# Bluetooth_mersasV2.net
KiCad netlist of a schematic drawn in Altium Designer
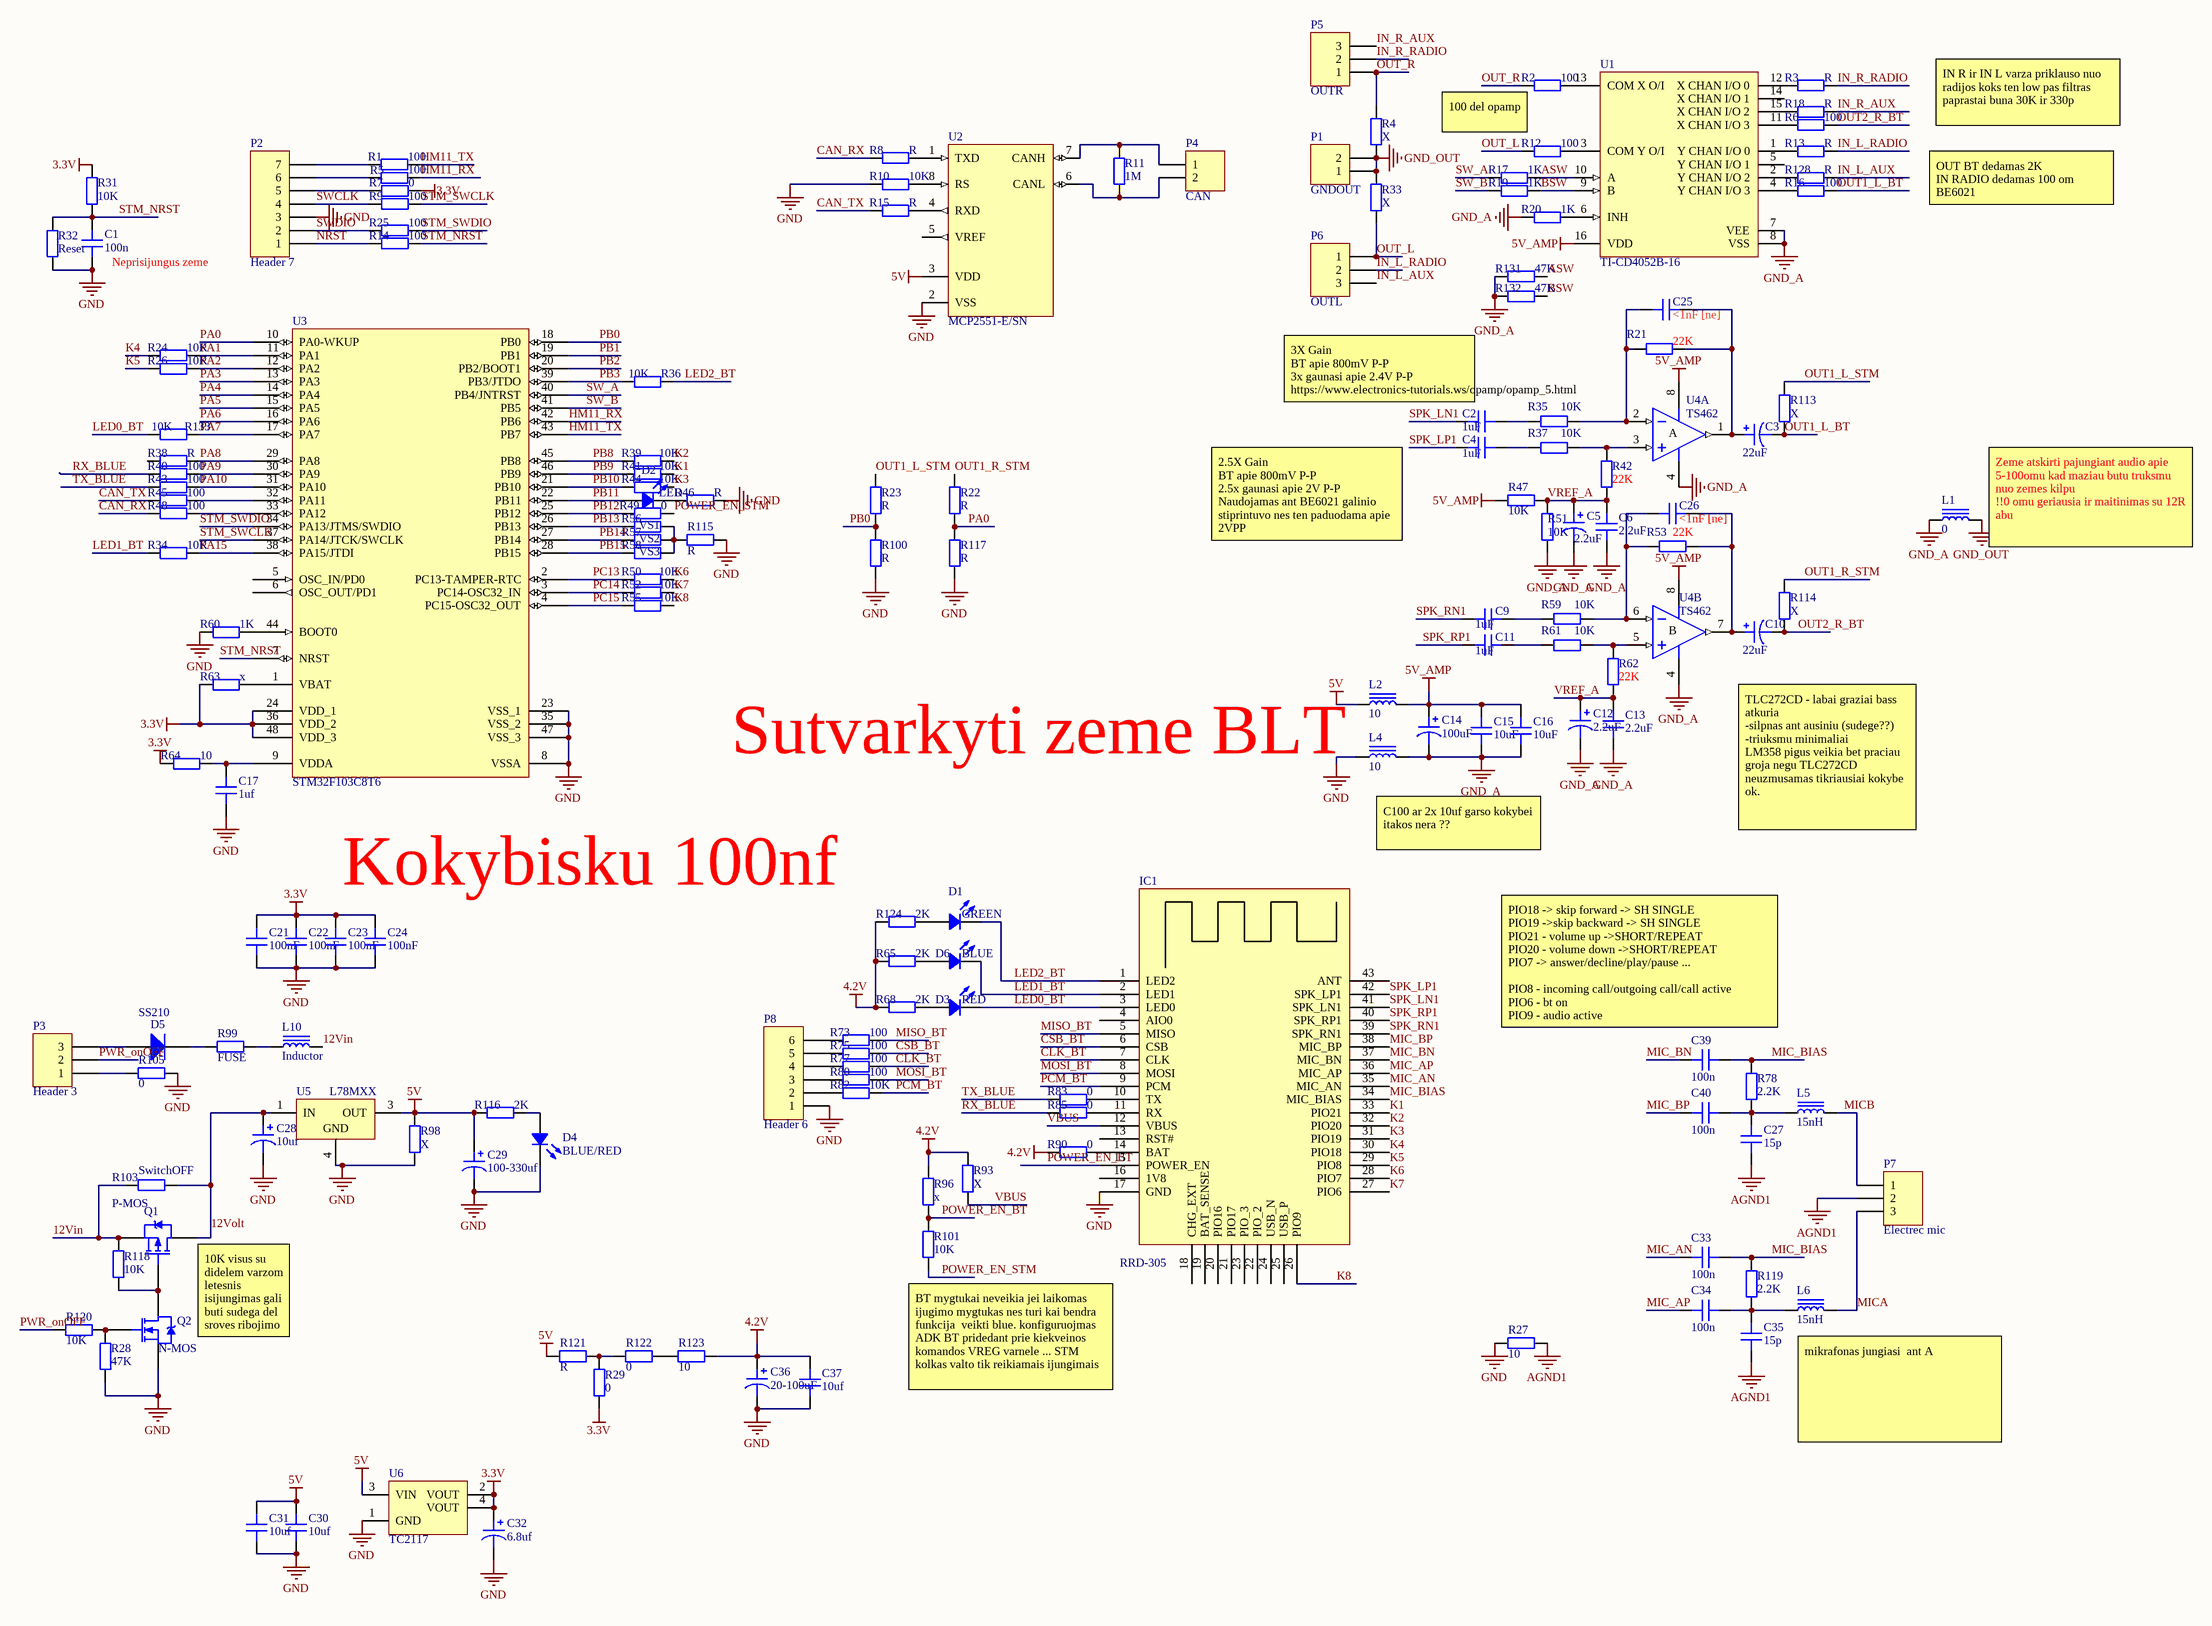
[diagram p0: Bluetooth_mersasV2.SchDoc]

(export (version "E")
  (design (tool "Eeschema 10.0.6"))
  (components
    (comp (ref "C1")
      (value "100n")
      (footprint "CAP 0603/1608")
      (description "Ceramic capacitor")
      (libsource (lib "Pasyviniai_RCL") (part "C"))
    )
    (comp (ref "C2")
      (value "1uF")
      (footprint "CAP 0805/2012")
      (description "Ceramic capacitor")
      (libsource (lib "Pasyviniai_RCL") (part "C"))
    )
    (comp (ref "C3")
      (value "22uF")
      (footprint "TANT A size")
      (description "Polarised Capacitor")
      (libsource (lib "") (part "Cpola_1"))
    )
    (comp (ref "C4")
      (value "1uF")
      (footprint "CAP 0805/2012")
      (description "Ceramic capacitor")
      (libsource (lib "Pasyviniai_RCL") (part "C"))
    )
    (comp (ref "C5")
      (value "2.2uF")
      (footprint "TANT R(2824)")
      (description "Polarised Capacitor")
      (libsource (lib "Pasyviniai_RCL") (part "Cpola"))
    )
    (comp (ref "C6")
      (value "2.2uF")
      (footprint "CAP 0805/2012")
      (description "Ceramic capacitor")
      (libsource (lib "Pasyviniai_RCL") (part "C"))
    )
    (comp (ref "C9")
      (value "1uF")
      (footprint "CAP 0805/2012")
      (description "Ceramic capacitor")
      (libsource (lib "Pasyviniai_RCL") (part "C"))
    )
    (comp (ref "C10")
      (value "22uF")
      (footprint "TANT A size")
      (description "Polarised Capacitor")
      (libsource (lib "") (part "Cpola_1"))
    )
    (comp (ref "C11")
      (value "1uF")
      (footprint "CAP 0805/2012")
      (description "Ceramic capacitor")
      (libsource (lib "Pasyviniai_RCL") (part "C"))
    )
    (comp (ref "C12")
      (value "2.2uF")
      (footprint "TANT R(2824)")
      (description "Polarised Capacitor")
      (libsource (lib "Pasyviniai_RCL") (part "Cpola"))
    )
    (comp (ref "C13")
      (value "2.2uF")
      (footprint "CAP 0805/2012")
      (description "Ceramic capacitor")
      (libsource (lib "Pasyviniai_RCL") (part "C"))
    )
    (comp (ref "C14")
      (value "100uF")
      (footprint "tant B size")
      (description "Polarised Capacitor")
      (libsource (lib "Pasyviniai_RCL") (part "Cpola"))
    )
    (comp (ref "C15")
      (value "10uF")
      (footprint "CAP 1206/3216")
      (description "Ceramic capacitor")
      (libsource (lib "Pasyviniai_RCL") (part "C"))
    )
    (comp (ref "C16")
      (value "10uF")
      (footprint "CAP 1206/3216")
      (description "Ceramic capacitor")
      (libsource (lib "Pasyviniai_RCL") (part "C"))
    )
    (comp (ref "C17")
      (value "1uf")
      (footprint "CAP 0805/2012")
      (description "Ceramic capacitor")
      (libsource (lib "Pasyviniai_RCL") (part "C"))
    )
    (comp (ref "C21")
      (value "100nF")
      (footprint "CAP 0603/1608")
      (description "Ceramic capacitor")
      (libsource (lib "Pasyviniai_RCL") (part "C"))
    )
    (comp (ref "C22")
      (value "100nF")
      (footprint "CAP 0603/1608")
      (description "Ceramic capacitor")
      (libsource (lib "Pasyviniai_RCL") (part "C"))
    )
    (comp (ref "C23")
      (value "100nF")
      (footprint "CAP 0603/1608")
      (description "Ceramic capacitor")
      (libsource (lib "Pasyviniai_RCL") (part "C"))
    )
    (comp (ref "C24")
      (value "100nF")
      (footprint "CAP 0603/1608")
      (description "Ceramic capacitor")
      (libsource (lib "Pasyviniai_RCL") (part "C"))
    )
    (comp (ref "C25")
      (value "<1nF [ne]")
      (footprint "CAP 0805/2012")
      (description "Ceramic capacitor")
      (libsource (lib "Pasyviniai_RCL") (part "C"))
    )
    (comp (ref "C26")
      (value "<1nF [ne]")
      (footprint "CAP 0805/2012")
      (description "Ceramic capacitor")
      (libsource (lib "Pasyviniai_RCL") (part "C"))
    )
    (comp (ref "C27")
      (value "15p")
      (footprint "CAP 0603/1608")
      (description "Ceramic capacitor")
      (libsource (lib "Pasyviniai_RCL") (part "C"))
    )
    (comp (ref "C28")
      (value "10uf")
      (footprint "CAP POL 2917/7343")
      (description "Polarised Capacitor")
      (libsource (lib "Pasyviniai_RCL") (part "Cpola"))
    )
    (comp (ref "C29")
      (value "100-330uf")
      (footprint "CAP POL 2917/7343")
      (description "Polarised Capacitor")
      (libsource (lib "Pasyviniai_RCL") (part "Cpola"))
    )
    (comp (ref "C30")
      (value "10uf")
      (footprint "CAP 1210/3225")
      (description "Ceramic capacitor")
      (libsource (lib "Pasyviniai_RCL") (part "C"))
    )
    (comp (ref "C31")
      (value "10uf")
      (footprint "CAP 1210/3225")
      (description "Ceramic capacitor")
      (libsource (lib "Pasyviniai_RCL") (part "C"))
    )
    (comp (ref "C32")
      (value "6.8uf")
      (footprint "CAP POL 2917/7343")
      (description "Polarised Capacitor")
      (libsource (lib "Pasyviniai_RCL") (part "Cpola"))
    )
    (comp (ref "C33")
      (value "100n")
      (footprint "CAP 0603/1608")
      (description "Ceramic capacitor")
      (libsource (lib "Pasyviniai_RCL") (part "C"))
    )
    (comp (ref "C34")
      (value "100n")
      (footprint "CAP 0603/1608")
      (description "Ceramic capacitor")
      (libsource (lib "Pasyviniai_RCL") (part "C"))
    )
    (comp (ref "C35")
      (value "15p")
      (footprint "CAP 0603/1608")
      (description "Ceramic capacitor")
      (libsource (lib "Pasyviniai_RCL") (part "C"))
    )
    (comp (ref "C36")
      (value "20-100uF")
      (footprint "tant B size")
      (description "Polarised Capacitor")
      (libsource (lib "Pasyviniai_RCL") (part "Cpola"))
    )
    (comp (ref "C37")
      (value "10uf")
      (footprint "CAP 1206/3216")
      (description "Ceramic capacitor")
      (libsource (lib "Pasyviniai_RCL") (part "C"))
    )
    (comp (ref "C39")
      (value "100n")
      (footprint "CAP 0603/1608")
      (description "Ceramic capacitor")
      (libsource (lib "Pasyviniai_RCL") (part "C"))
    )
    (comp (ref "C40")
      (value "100n")
      (footprint "CAP 0603/1608")
      (description "Ceramic capacitor")
      (libsource (lib "Pasyviniai_RCL") (part "C"))
    )
    (comp (ref "D1")
      (value "GREEN")
      (footprint "LED 0805/2012")
      (description "Chip LED")
      (libsource (lib "Pasyviniai_RCL") (part "LED"))
    )
    (comp (ref "D2")
      (value "LED")
      (footprint "LED 0603/1608")
      (description "Chip LED")
      (libsource (lib "Pasyviniai_RCL") (part "LED"))
    )
    (comp (ref "D3")
      (value "RED")
      (footprint "LED 0805/2012")
      (description "Chip LED")
      (libsource (lib "Pasyviniai_RCL") (part "LED"))
    )
    (comp (ref "D4")
      (value "BLUE/RED")
      (footprint "LED 0805/2012")
      (description "Chip LED")
      (libsource (lib "Pasyviniai_RCL") (part "LED"))
    )
    (comp (ref "D5")
      (value "SS210")
      (footprint "DO214AC SMA")
      (description "Diode")
      (libsource (lib "Pasyviniai_RCL") (part "Diode"))
    )
    (comp (ref "D6")
      (value "BLUE")
      (footprint "LED 0805/2012")
      (description "Chip LED")
      (libsource (lib "Pasyviniai_RCL") (part "LED"))
    )
    (comp (ref "IC1")
      (value "RRD-305")
      (footprint "RRD-305")
      (description "Audio Module Bluetooth 5.0 QCC3005 chip")
      (libsource (lib "Ivairus") (part "RRD-305"))
    )
    (comp (ref "L1")
      (value "0")
      (footprint "IND 1206/3216 - 1.0MM")
      (description "SMT Inductor")
      (libsource (lib "Pasyviniai_RCL") (part "Inductor"))
    )
    (comp (ref "L2")
      (value "10")
      (footprint "IND 1206/3216 - 1.0MM")
      (description "SMT Inductor")
      (libsource (lib "Pasyviniai_RCL") (part "Inductor"))
    )
    (comp (ref "L4")
      (value "10")
      (footprint "IND 1206/3216 - 1.0MM")
      (description "SMT Inductor")
      (libsource (lib "Pasyviniai_RCL") (part "Inductor"))
    )
    (comp (ref "L5")
      (value "15nH")
      (footprint "IND 1206/3216 - 1.0MM")
      (description "SMT Inductor")
      (libsource (lib "Pasyviniai_RCL") (part "Inductor"))
    )
    (comp (ref "L6")
      (value "15nH")
      (footprint "IND 1206/3216 - 1.0MM")
      (description "SMT Inductor")
      (libsource (lib "Pasyviniai_RCL") (part "Inductor"))
    )
    (comp (ref "L10")
      (value "Inductor")
      (footprint "IND 1206/3216 - 1.0MM")
      (description "SMT Inductor")
      (libsource (lib "Pasyviniai_RCL") (part "Inductor"))
    )
    (comp (ref "P1")
      (value "GNDOUT")
      (footprint "HDR1X2")
      (description "Header, 2-Pin")
      (fields (field (name "PUBLISHER") "Altium Limited"))
      (libsource (lib "") (part "Header 2_1"))
    )
    (comp (ref "P2")
      (value "Header 7")
      (footprint "2mm1X7")
      (description "Header, 7-Pin")
      (fields (field (name "PUBLISHER") "Altium Limited"))
      (libsource (lib "PIN_HEADER") (part "Header 7"))
    )
    (comp (ref "P3")
      (value "Header 3")
      (footprint "HDR1X3")
      (description "Header, 3-Pin")
      (fields (field (name "PUBLISHER") "Altium Limited"))
      (libsource (lib "PIN_HEADER") (part "Header 3"))
    )
    (comp (ref "P4")
      (value "CAN")
      (footprint "HDR1X2")
      (description "Header, 2-Pin")
      (fields (field (name "PUBLISHER") "Altium Limited"))
      (libsource (lib "PIN_HEADER") (part "Header 2"))
    )
    (comp (ref "P5")
      (value "OUTR")
      (footprint "HDR1X3")
      (description "Header, 3-Pin")
      (fields (field (name "PUBLISHER") "Altium Limited"))
      (libsource (lib "PIN_HEADER") (part "Header 3"))
    )
    (comp (ref "P6")
      (value "OUTL")
      (footprint "HDR1X3")
      (description "Header, 3-Pin")
      (fields (field (name "PUBLISHER") "Altium Limited"))
      (libsource (lib "") (part "Header 3_2"))
    )
    (comp (ref "P7")
      (value "Electrec mic")
      (footprint "HDR1X3")
      (description "Header, 3-Pin")
      (fields (field (name "PUBLISHER") "Altium Limited"))
      (libsource (lib "") (part "Header 3_1"))
    )
    (comp (ref "P8")
      (value "Header 6")
      (footprint "2mm1X6")
      (description "Header, 6-Pin")
      (fields (field (name "PUBLISHER") "Altium Limited"))
      (libsource (lib "PIN_HEADER") (part "Header 6"))
    )
    (comp (ref "Q1")
      (value "P-MOS")
      (footprint "TI SOT-23-3 DBZ")
      (description "Power MOSFET 1GAte 2Source 3 DRAIN")
      (fields (field (name "PUBLISHER") "Altium Limited"))
      (libsource (lib "Aktyviniai") (part "Mosfet-Pch SOT23"))
    )
    (comp (ref "Q2")
      (value "N-MOS")
      (footprint "TI SOT-23-3 DBZ")
      (description "Power MOSFET 1GAte 2Source 3 DRAIN")
      (fields (field (name "PUBLISHER") "Altium Limited"))
      (libsource (lib "Aktyviniai") (part "Mosfet-Nch SOT23"))
    )
    (comp (ref "R1")
      (value "100")
      (footprint "RES 0603/1608")
      (description "Resistor")
      (libsource (lib "") (part "R_1"))
    )
    (comp (ref "R2")
      (value "100")
      (footprint "RES 0805/2012")
      (description "Resistor")
      (libsource (lib "") (part "R_1"))
    )
    (comp (ref "R3")
      (value "R")
      (footprint "RES 0805/2012")
      (description "Resistor")
      (libsource (lib "") (part "R_1"))
    )
    (comp (ref "R4")
      (value "X")
      (footprint "RES 0805/2012")
      (description "Resistor")
      (libsource (lib "Pasyviniai_RCL") (part "R"))
    )
    (comp (ref "R5")
      (value "100")
      (footprint "RES 0603/1608")
      (description "Resistor")
      (libsource (lib "") (part "R_1"))
    )
    (comp (ref "R6")
      (value "100")
      (footprint "RES 0805/2012")
      (description "Resistor")
      (libsource (lib "") (part "R_1"))
    )
    (comp (ref "R7")
      (value "0")
      (footprint "RES 0603/1608")
      (description "Resistor")
      (libsource (lib "") (part "R_1"))
    )
    (comp (ref "R8")
      (value "R")
      (footprint "RES 0805/2012")
      (description "Resistor")
      (libsource (lib "") (part "R_1"))
    )
    (comp (ref "R9")
      (value "100")
      (footprint "RES 0603/1608")
      (description "Resistor")
      (libsource (lib "") (part "R_1"))
    )
    (comp (ref "R10")
      (value "10K")
      (footprint "RES 0805/2012")
      (description "Resistor")
      (libsource (lib "") (part "R_1"))
    )
    (comp (ref "R11")
      (value "1M")
      (footprint "RES 0603/1608")
      (description "Resistor")
      (libsource (lib "Pasyviniai_RCL") (part "R"))
    )
    (comp (ref "R12")
      (value "100")
      (footprint "RES 0805/2012")
      (description "Resistor")
      (libsource (lib "") (part "R_1"))
    )
    (comp (ref "R13")
      (value "R")
      (footprint "RES 0805/2012")
      (description "Resistor")
      (libsource (lib "") (part "R_1"))
    )
    (comp (ref "R14")
      (value "100")
      (footprint "RES 0603/1608")
      (description "Resistor")
      (libsource (lib "") (part "R_1"))
    )
    (comp (ref "R15")
      (value "R")
      (footprint "RES 0603/1608")
      (description "Resistor")
      (libsource (lib "") (part "R_1"))
    )
    (comp (ref "R16")
      (value "100")
      (footprint "RES 0805/2012")
      (description "Resistor")
      (libsource (lib "") (part "R_1"))
    )
    (comp (ref "R17")
      (value "1K")
      (footprint "RES 0603/1608")
      (description "Resistor")
      (libsource (lib "") (part "R_1"))
    )
    (comp (ref "R18")
      (value "R")
      (footprint "RES 0805/2012")
      (description "Resistor")
      (libsource (lib "") (part "R_1"))
    )
    (comp (ref "R19")
      (value "1K")
      (footprint "RES 0603/1608")
      (description "Resistor")
      (libsource (lib "") (part "R_1"))
    )
    (comp (ref "R20")
      (value "1K")
      (footprint "RES 0603/1608")
      (description "Resistor")
      (libsource (lib "") (part "R_1"))
    )
    (comp (ref "R21")
      (value "22K")
      (footprint "RES 0805/2012")
      (description "Resistor")
      (libsource (lib "") (part "R_1"))
    )
    (comp (ref "R22")
      (value "R")
      (footprint "RES 0603/1608")
      (description "Resistor")
      (libsource (lib "Pasyviniai_RCL") (part "R"))
    )
    (comp (ref "R23")
      (value "R")
      (footprint "RES 0603/1608")
      (description "Resistor")
      (libsource (lib "Pasyviniai_RCL") (part "R"))
    )
    (comp (ref "R24")
      (value "10K")
      (footprint "RES 0603/1608")
      (description "Resistor")
      (libsource (lib "") (part "R_1"))
    )
    (comp (ref "R25")
      (value "100")
      (footprint "RES 0805/2012")
      (description "Resistor")
      (libsource (lib "") (part "R_1"))
    )
    (comp (ref "R26")
      (value "10K")
      (footprint "RES 0603/1608")
      (description "Resistor")
      (libsource (lib "") (part "R_1"))
    )
    (comp (ref "R27")
      (value "10")
      (footprint "RES 0805/2012")
      (description "Resistor")
      (libsource (lib "") (part "R_3"))
    )
    (comp (ref "R28")
      (value "47K")
      (footprint "RES 0603/1608")
      (description "Resistor")
      (libsource (lib "") (part "R_2"))
    )
    (comp (ref "R29")
      (value "0")
      (footprint "RES 1206/3216")
      (description "Resistor")
      (libsource (lib "Pasyviniai_RCL") (part "R"))
    )
    (comp (ref "R31")
      (value "10K")
      (footprint "RES 0603/1608")
      (description "Resistor")
      (libsource (lib "") (part "R_2"))
    )
    (comp (ref "R32")
      (value "Reset")
      (footprint "RES 0805/2012")
      (description "Resistor")
      (libsource (lib "") (part "R_2"))
    )
    (comp (ref "R33")
      (value "X")
      (footprint "RES 0805/2012")
      (description "Resistor")
      (libsource (lib "Pasyviniai_RCL") (part "R"))
    )
    (comp (ref "R34")
      (value "10K")
      (footprint "RES 0603/1608")
      (description "Resistor")
      (libsource (lib "") (part "R_1"))
    )
    (comp (ref "R35")
      (value "10K")
      (footprint "RES 0805/2012")
      (description "Resistor")
      (libsource (lib "") (part "R_1"))
    )
    (comp (ref "R36")
      (value "10K")
      (footprint "RES 0603/1608")
      (description "Resistor")
      (libsource (lib "") (part "R_3"))
    )
    (comp (ref "R37")
      (value "10K")
      (footprint "RES 0805/2012")
      (description "Resistor")
      (libsource (lib "") (part "R_1"))
    )
    (comp (ref "R38")
      (value "R")
      (footprint "RES 0603/1608")
      (description "Resistor")
      (libsource (lib "") (part "R_1"))
    )
    (comp (ref "R39")
      (value "10K")
      (footprint "RES 0603/1608")
      (description "Resistor")
      (libsource (lib "") (part "R_1"))
    )
    (comp (ref "R40")
      (value "100")
      (footprint "RES 0603/1608")
      (description "Resistor")
      (libsource (lib "") (part "R_1"))
    )
    (comp (ref "R41")
      (value "10K")
      (footprint "RES 0603/1608")
      (description "Resistor")
      (libsource (lib "") (part "R_1"))
    )
    (comp (ref "R42")
      (value "22K")
      (footprint "RES 0805/2012")
      (description "Resistor")
      (libsource (lib "Pasyviniai_RCL") (part "R"))
    )
    (comp (ref "R43")
      (value "100")
      (footprint "RES 0603/1608")
      (description "Resistor")
      (libsource (lib "") (part "R_1"))
    )
    (comp (ref "R44")
      (value "10K")
      (footprint "RES 0603/1608")
      (description "Resistor")
      (libsource (lib "") (part "R_1"))
    )
    (comp (ref "R45")
      (value "100")
      (footprint "RES 0603/1608")
      (description "Resistor")
      (libsource (lib "") (part "R_1"))
    )
    (comp (ref "R46")
      (value "R")
      (footprint "RES 0603/1608")
      (description "Resistor")
      (libsource (lib "") (part "R_1"))
    )
    (comp (ref "R47")
      (value "10K")
      (footprint "RES 0805/2012")
      (description "Resistor")
      (libsource (lib "") (part "R_3"))
    )
    (comp (ref "R48")
      (value "100")
      (footprint "RES 0603/1608")
      (description "Resistor")
      (libsource (lib "") (part "R_1"))
    )
    (comp (ref "R49")
      (value "0")
      (footprint "RES 0603/1608")
      (description "Resistor")
      (libsource (lib "") (part "R_1"))
    )
    (comp (ref "R50")
      (value "10K")
      (footprint "RES 0603/1608")
      (description "Resistor")
      (libsource (lib "") (part "R_1"))
    )
    (comp (ref "R51")
      (value "10K")
      (footprint "RES 0805/2012")
      (description "Resistor")
      (libsource (lib "") (part "R_2"))
    )
    (comp (ref "R52")
      (value "10K")
      (footprint "RES 0603/1608")
      (description "Resistor")
      (libsource (lib "") (part "R_1"))
    )
    (comp (ref "R53")
      (value "22K")
      (footprint "RES 0805/2012")
      (description "Resistor")
      (libsource (lib "") (part "R_1"))
    )
    (comp (ref "R55")
      (value "10K")
      (footprint "RES 0603/1608")
      (description "Resistor")
      (libsource (lib "") (part "R_1"))
    )
    (comp (ref "R56")
      (value "VS1")
      (footprint "RES 0603/1608")
      (description "Resistor")
      (libsource (lib "") (part "R_1"))
    )
    (comp (ref "R57")
      (value "VS2")
      (footprint "RES 0603/1608")
      (description "Resistor")
      (libsource (lib "") (part "R_1"))
    )
    (comp (ref "R58")
      (value "VS3")
      (footprint "RES 0603/1608")
      (description "Resistor")
      (libsource (lib "") (part "R_1"))
    )
    (comp (ref "R59")
      (value "10K")
      (footprint "RES 0805/2012")
      (description "Resistor")
      (libsource (lib "") (part "R_1"))
    )
    (comp (ref "R60")
      (value "1K")
      (footprint "RES 0603/1608")
      (description "Resistor")
      (libsource (lib "") (part "R_1"))
    )
    (comp (ref "R61")
      (value "10K")
      (footprint "RES 0805/2012")
      (description "Resistor")
      (libsource (lib "") (part "R_1"))
    )
    (comp (ref "R62")
      (value "22K")
      (footprint "RES 0805/2012")
      (description "Resistor")
      (libsource (lib "Pasyviniai_RCL") (part "R"))
    )
    (comp (ref "R63")
      (value "x")
      (footprint "RES 0603/1608")
      (description "Resistor")
      (libsource (lib "") (part "R_1"))
    )
    (comp (ref "R64")
      (value "10")
      (footprint "RES 1206/3216")
      (description "Resistor")
      (libsource (lib "") (part "R_1"))
    )
    (comp (ref "R65")
      (value "2K")
      (footprint "RES 0805/2012")
      (description "Resistor")
      (libsource (lib "") (part "R_1"))
    )
    (comp (ref "R68")
      (value "2K")
      (footprint "RES 0805/2012")
      (description "Resistor")
      (libsource (lib "") (part "R_1"))
    )
    (comp (ref "R73")
      (value "100")
      (footprint "RES 0603/1608")
      (description "Resistor")
      (libsource (lib "") (part "R_1"))
    )
    (comp (ref "R75")
      (value "100")
      (footprint "RES 0603/1608")
      (description "Resistor")
      (libsource (lib "") (part "R_1"))
    )
    (comp (ref "R77")
      (value "100")
      (footprint "RES 0603/1608")
      (description "Resistor")
      (libsource (lib "") (part "R_1"))
    )
    (comp (ref "R78")
      (value "2.2K")
      (footprint "RES 0805/2012")
      (description "Resistor")
      (libsource (lib "Pasyviniai_RCL") (part "R"))
    )
    (comp (ref "R80")
      (value "100")
      (footprint "RES 0603/1608")
      (description "Resistor")
      (libsource (lib "") (part "R_1"))
    )
    (comp (ref "R82")
      (value "10K")
      (footprint "RES 0603/1608")
      (description "Resistor")
      (libsource (lib "") (part "R_1"))
    )
    (comp (ref "R83")
      (value "0")
      (footprint "RES 0603/1608")
      (description "Resistor")
      (libsource (lib "") (part "R_1"))
    )
    (comp (ref "R85")
      (value "0")
      (footprint "RES 0603/1608")
      (description "Resistor")
      (libsource (lib "") (part "R_1"))
    )
    (comp (ref "R90")
      (value "0")
      (footprint "RES 0603/1608")
      (description "Resistor")
      (libsource (lib "") (part "R_1"))
    )
    (comp (ref "R93")
      (value "X")
      (footprint "RES 0603/1608")
      (description "Resistor")
      (libsource (lib "") (part "R_2"))
    )
    (comp (ref "R96")
      (value "x")
      (footprint "RES 0603/1608")
      (description "Resistor")
      (libsource (lib "Pasyviniai_RCL") (part "R"))
    )
    (comp (ref "R98")
      (value "X")
      (footprint "RES 1206/3216")
      (description "Resistor")
      (libsource (lib "Pasyviniai_RCL") (part "R"))
    )
    (comp (ref "R99")
      (value "FUSE")
      (footprint "RES 1206/3216")
      (description "Resistor")
      (libsource (lib "") (part "R_3"))
    )
    (comp (ref "R100")
      (value "R")
      (footprint "RES 0603/1608")
      (description "Resistor")
      (libsource (lib "Pasyviniai_RCL") (part "R"))
    )
    (comp (ref "R101")
      (value "10K")
      (footprint "RES 0603/1608")
      (description "Resistor")
      (libsource (lib "Pasyviniai_RCL") (part "R"))
    )
    (comp (ref "R103")
      (value "SwitchOFF")
      (footprint "RES 0805/2012")
      (description "Resistor")
      (libsource (lib "") (part "R_3"))
    )
    (comp (ref "R105")
      (value "0")
      (footprint "RES 1206/3216")
      (description "Resistor")
      (libsource (lib "") (part "R_3"))
    )
    (comp (ref "R113")
      (value "X")
      (footprint "RES 0603/1608")
      (description "Resistor")
      (libsource (lib "Pasyviniai_RCL") (part "R"))
    )
    (comp (ref "R114")
      (value "X")
      (footprint "RES 0603/1608")
      (description "Resistor")
      (libsource (lib "Pasyviniai_RCL") (part "R"))
    )
    (comp (ref "R115")
      (value "R")
      (footprint "RES 0603/1608")
      (description "Resistor")
      (libsource (lib "") (part "R_3"))
    )
    (comp (ref "R116")
      (value "2K")
      (footprint "RES 0805/2012")
      (description "Resistor")
      (libsource (lib "") (part "R_1"))
    )
    (comp (ref "R117")
      (value "R")
      (footprint "RES 0603/1608")
      (description "Resistor")
      (libsource (lib "Pasyviniai_RCL") (part "R"))
    )
    (comp (ref "R118")
      (value "10K")
      (footprint "RES 0603/1608")
      (description "Resistor")
      (libsource (lib "") (part "R_2"))
    )
    (comp (ref "R119")
      (value "2.2K")
      (footprint "RES 0805/2012")
      (description "Resistor")
      (libsource (lib "Pasyviniai_RCL") (part "R"))
    )
    (comp (ref "R120")
      (value "10K")
      (footprint "RES 0805/2012")
      (description "Resistor")
      (libsource (lib "") (part "R_1"))
    )
    (comp (ref "R121")
      (value "R")
      (footprint "RES 1206/3216")
      (description "Resistor")
      (libsource (lib "") (part "R_3"))
    )
    (comp (ref "R122")
      (value "0")
      (footprint "RES 1206/3216")
      (description "Resistor")
      (libsource (lib "") (part "R_3"))
    )
    (comp (ref "R123")
      (value "10")
      (footprint "RES 1206/3216")
      (description "Resistor")
      (libsource (lib "") (part "R_3"))
    )
    (comp (ref "R124")
      (value "2K")
      (footprint "RES 0805/2012")
      (description "Resistor")
      (libsource (lib "") (part "R_1"))
    )
    (comp (ref "R128")
      (value "R")
      (footprint "RES 0805/2012")
      (description "Resistor")
      (libsource (lib "") (part "R_1"))
    )
    (comp (ref "R131")
      (value "47K")
      (footprint "RES 0603/1608")
      (description "Resistor")
      (libsource (lib "") (part "R_1"))
    )
    (comp (ref "R132")
      (value "47K")
      (footprint "RES 0603/1608")
      (description "Resistor")
      (libsource (lib "") (part "R_1"))
    )
    (comp (ref "R133")
      (value "10K")
      (footprint "RES 0603/1608")
      (description "Resistor")
      (libsource (lib "") (part "R_1"))
    )
    (comp (ref "U1")
      (value "TI-CD4052B-16")
      (footprint "D0016A_N")
      (libsource (lib "Mikroschemos") (part "TI-CD4052B-16"))
    )
    (comp (ref "U2")
      (value "MCP2551-E/SN")
      (footprint "SOIC-SN8_L")
      (description "High-Speed CAN Transceiver, 8-Pin SOIC, Extended Temperature")
      (fields (field (name "MANUFACTURER") "Microchip"))
      (libsource (lib "Microchip Interface") (part "MCP2551-E/SN"))
    )
    (comp (ref "U3")
      (value "STM32F103C8T6")
      (footprint "NXP LQFP-48 7x7mm")
      (description "STM32 ARM-based 32-bit MCU with 64 Kbytes Flash, 48-pin LQFP, Industrial Temperature")
      (fields (field (name "PUBLISHER") "Altium Limited"))
      (libsource (lib "Mikroschemos") (part "STM32F103C8T6"))
    )
    (comp (ref "U4")
      (value "TS462")
      (footprint "DIODES SO-8")
      (description "Low-Noise Dual Operational Amplifier")
      (fields (field (name "PUBLISHER") "Altium Limited"))
      (libsource (lib "Mikroschemos") (part "TS462"))
    )
    (comp (ref "U5")
      (value "L78MXX")
      (footprint "TO-252")
      (description "Positive Voltage Regulator")
      (fields (field (name "PUBLISHER") "Altium Limited"))
      (libsource (lib "Mikroschemos") (part "L78MXX"))
    )
    (comp (ref "U6") (value "TC2117") (footprint "ST SOT-223") (libsource (lib "Ivairus") (part "TC2117")))
  )
  (nets
    (net (code "1") (name "/12Vin") (class "Default")
      (node (ref "L10") (pin "2") (pinfunction "2_2") (pintype "passive"))
      (node (ref "Q1") (pin "2") (pinfunction "S_2") (pintype "passive"))
      (node (ref "R103") (pin "1") (pinfunction "1_1") (pintype "passive"))
      (node (ref "R118") (pin "2") (pinfunction "2_2") (pintype "passive"))
    )
    (net (code "2") (name "/12Volt") (class "Default")
      (node (ref "C28") (pin "1") (pinfunction "1_1") (pintype "passive"))
      (node (ref "Q1") (pin "3") (pinfunction "D_3") (pintype "passive"))
      (node (ref "R103") (pin "2") (pinfunction "2_2") (pintype "passive"))
      (node (ref "U5") (pin "1") (pinfunction "IN_1") (pintype "power_in"))
    )
    (net (code "3") (name "/ASW") (class "Default")
      (node (ref "R131") (pin "1") (pinfunction "1_1") (pintype "passive"))
      (node (ref "R17") (pin "1") (pinfunction "1_1") (pintype "passive"))
      (node (ref "U1") (pin "10") (pinfunction "A_10") (pintype "input"))
    )
    (net (code "4") (name "/BSW") (class "Default")
      (node (ref "R132") (pin "1") (pinfunction "1_1") (pintype "passive"))
      (node (ref "R19") (pin "1") (pinfunction "1_1") (pintype "passive"))
      (node (ref "U1") (pin "9") (pinfunction "B_9") (pintype "input"))
    )
    (net (code "5") (name "/CAN_RX") (class "Default")
      (node (ref "R48") (pin "2") (pinfunction "2_2") (pintype "passive"))
      (node (ref "R8") (pin "2") (pinfunction "2_2") (pintype "passive"))
    )
    (net (code "6") (name "/CAN_TX") (class "Default")
      (node (ref "R15") (pin "2") (pinfunction "2_2") (pintype "passive"))
      (node (ref "R45") (pin "2") (pinfunction "2_2") (pintype "passive"))
    )
    (net (code "7") (name "/CLK_BT") (class "Default")
      (node (ref "IC1") (pin "7") (pinfunction "CLK_7") (pintype "passive"))
      (node (ref "R77") (pin "1") (pinfunction "1_1") (pintype "passive"))
    )
    (net (code "8") (name "/CSB_BT") (class "Default")
      (node (ref "IC1") (pin "6") (pinfunction "CSB_6") (pintype "passive"))
      (node (ref "R75") (pin "1") (pinfunction "1_1") (pintype "passive"))
    )
    (net (code "9") (name "/HM11_RX") (class "Default")
      (node (ref "R5") (pin "1") (pinfunction "1_1") (pintype "passive"))
      (node (ref "U3") (pin "42") (pinfunction "PB6_42") (pintype "bidirectional"))
    )
    (net (code "10") (name "/HM11_TX") (class "Default")
      (node (ref "R1") (pin "1") (pinfunction "1_1") (pintype "passive"))
      (node (ref "U3") (pin "43") (pinfunction "PB7_43") (pintype "bidirectional"))
    )
    (net (code "11") (name "/IN_L_AUX") (class "Default")
      (node (ref "P6") (pin "3") (pinfunction "3_3") (pintype "passive"))
      (node (ref "R128") (pin "1") (pinfunction "1_1") (pintype "passive"))
    )
    (net (code "12") (name "/IN_L_RADIO") (class "Default")
      (node (ref "P6") (pin "2") (pinfunction "2_2") (pintype "passive"))
      (node (ref "R13") (pin "1") (pinfunction "1_1") (pintype "passive"))
    )
    (net (code "13") (name "/IN_R_AUX") (class "Default")
      (node (ref "P5") (pin "3") (pinfunction "3_3") (pintype "passive"))
      (node (ref "R18") (pin "1") (pinfunction "1_1") (pintype "passive"))
    )
    (net (code "14") (name "/IN_R_RADIO") (class "Default")
      (node (ref "P5") (pin "2") (pinfunction "2_2") (pintype "passive"))
      (node (ref "R3") (pin "1") (pinfunction "1_1") (pintype "passive"))
    )
    (net (code "15") (name "/K1") (class "Default")
      (node (ref "IC1") (pin "33") (pinfunction "PIO21_33") (pintype "passive"))
      (node (ref "R41") (pin "1") (pinfunction "1_1") (pintype "passive"))
    )
    (net (code "16") (name "/K2") (class "Default")
      (node (ref "IC1") (pin "32") (pinfunction "PIO20_32") (pintype "passive"))
      (node (ref "R39") (pin "1") (pinfunction "1_1") (pintype "passive"))
    )
    (net (code "17") (name "/K3") (class "Default")
      (node (ref "IC1") (pin "31") (pinfunction "PIO19_31") (pintype "passive"))
      (node (ref "R44") (pin "1") (pinfunction "1_1") (pintype "passive"))
    )
    (net (code "18") (name "/K4") (class "Default")
      (node (ref "IC1") (pin "30") (pinfunction "PIO18_30") (pintype "passive"))
      (node (ref "R24") (pin "2") (pinfunction "2_2") (pintype "passive"))
    )
    (net (code "19") (name "/K5") (class "Default")
      (node (ref "IC1") (pin "29") (pinfunction "PIO8_29") (pintype "passive"))
      (node (ref "R26") (pin "2") (pinfunction "2_2") (pintype "passive"))
    )
    (net (code "20") (name "/K6") (class "Default")
      (node (ref "IC1") (pin "28") (pinfunction "PIO7_28") (pintype "passive"))
      (node (ref "R50") (pin "1") (pinfunction "1_1") (pintype "passive"))
    )
    (net (code "21") (name "/K7") (class "Default")
      (node (ref "IC1") (pin "27") (pinfunction "PIO6_27") (pintype "passive"))
      (node (ref "R52") (pin "1") (pinfunction "1_1") (pintype "passive"))
    )
    (net (code "22") (name "/K8") (class "Default")
      (node (ref "IC1") (pin "26") (pinfunction "PIO9_26") (pintype "passive"))
      (node (ref "R55") (pin "1") (pinfunction "1_1") (pintype "passive"))
    )
    (net (code "24") (name "/LED0_BT") (class "Default")
      (node (ref "D3") (pin "2") (pinfunction "2_2") (pintype "passive"))
      (node (ref "IC1") (pin "3") (pinfunction "LED0_3") (pintype "passive"))
      (node (ref "R133") (pin "2") (pinfunction "2_2") (pintype "passive"))
    )
    (net (code "25") (name "/LED1_BT") (class "Default")
      (node (ref "D6") (pin "2") (pinfunction "2_2") (pintype "passive"))
      (node (ref "IC1") (pin "2") (pinfunction "LED1_2") (pintype "passive"))
      (node (ref "R34") (pin "2") (pinfunction "2_2") (pintype "passive"))
    )
    (net (code "26") (name "/LED2_BT") (class "Default")
      (node (ref "D1") (pin "2") (pinfunction "2_2") (pintype "passive"))
      (node (ref "IC1") (pin "1") (pinfunction "LED2_1") (pintype "passive"))
      (node (ref "R36") (pin "2") (pinfunction "2_2") (pintype "passive"))
    )
    (net (code "27") (name "/MICA") (class "Default")
      (node (ref "L6") (pin "2") (pinfunction "2_2") (pintype "passive"))
      (node (ref "P7") (pin "3") (pinfunction "3_3") (pintype "passive"))
    )
    (net (code "28") (name "/MICB") (class "Default")
      (node (ref "L5") (pin "2") (pinfunction "2_2") (pintype "passive"))
      (node (ref "P7") (pin "1") (pinfunction "1_1") (pintype "passive"))
    )
    (net (code "29") (name "/MIC_AN") (class "Default")
      (node (ref "C33") (pin "2") (pinfunction "2_2") (pintype "passive"))
      (node (ref "IC1") (pin "35") (pinfunction "MIC_AN_35") (pintype "passive"))
    )
    (net (code "30") (name "/MIC_AP") (class "Default")
      (node (ref "C34") (pin "2") (pinfunction "2_2") (pintype "passive"))
      (node (ref "IC1") (pin "36") (pinfunction "MIC_AP_36") (pintype "passive"))
    )
    (net (code "31") (name "/MIC_BIAS") (class "Default")
      (node (ref "C33") (pin "1") (pinfunction "1_1") (pintype "passive"))
      (node (ref "C39") (pin "1") (pinfunction "1_1") (pintype "passive"))
      (node (ref "IC1") (pin "34") (pinfunction "MIC_BIAS_34") (pintype "passive"))
      (node (ref "R119") (pin "1") (pinfunction "1_1") (pintype "passive"))
      (node (ref "R78") (pin "1") (pinfunction "1_1") (pintype "passive"))
    )
    (net (code "32") (name "/MIC_BN") (class "Default")
      (node (ref "C39") (pin "2") (pinfunction "2_2") (pintype "passive"))
      (node (ref "IC1") (pin "37") (pinfunction "MIC_BN_37") (pintype "passive"))
    )
    (net (code "33") (name "/MIC_BP") (class "Default")
      (node (ref "C40") (pin "2") (pinfunction "2_2") (pintype "passive"))
      (node (ref "IC1") (pin "38") (pinfunction "MIC_BP_38") (pintype "passive"))
    )
    (net (code "34") (name "/MISO_BT") (class "Default")
      (node (ref "IC1") (pin "5") (pinfunction "MISO_5") (pintype "passive"))
      (node (ref "R73") (pin "1") (pinfunction "1_1") (pintype "passive"))
    )
    (net (code "35") (name "/MOSI_BT") (class "Default")
      (node (ref "IC1") (pin "8") (pinfunction "MOSI_8") (pintype "passive"))
      (node (ref "R80") (pin "1") (pinfunction "1_1") (pintype "passive"))
    )
    (net (code "36") (name "/NRST") (class "Default")
      (node (ref "P2") (pin "1") (pinfunction "1_1") (pintype "passive"))
      (node (ref "R14") (pin "2") (pinfunction "2_2") (pintype "passive"))
    )
    (net (code "38") (name "/OUT1_L_BT") (class "Default")
      (node (ref "C3") (pin "2") (pinfunction "2_2") (pintype "passive"))
      (node (ref "R113") (pin "2") (pinfunction "2_2") (pintype "passive"))
      (node (ref "R16") (pin "1") (pinfunction "1_1") (pintype "passive"))
    )
    (net (code "39") (name "/OUT1_L_STM") (class "Default")
      (node (ref "R113") (pin "1") (pinfunction "1_1") (pintype "passive"))
      (node (ref "R23") (pin "1") (pinfunction "1_1") (pintype "passive"))
    )
    (net (code "40") (name "/OUT1_R_STM") (class "Default")
      (node (ref "R114") (pin "1") (pinfunction "1_1") (pintype "passive"))
      (node (ref "R22") (pin "1") (pinfunction "1_1") (pintype "passive"))
    )
    (net (code "41") (name "/OUT2_R_BT") (class "Default")
      (node (ref "C10") (pin "2") (pinfunction "2_2") (pintype "passive"))
      (node (ref "R114") (pin "2") (pinfunction "2_2") (pintype "passive"))
      (node (ref "R6") (pin "1") (pinfunction "1_1") (pintype "passive"))
    )
    (net (code "42") (name "/OUT_L") (class "Default")
      (node (ref "P6") (pin "1") (pinfunction "1_1") (pintype "passive"))
      (node (ref "R12") (pin "2") (pinfunction "2_2") (pintype "passive"))
      (node (ref "R33") (pin "2") (pinfunction "2_2") (pintype "passive"))
    )
    (net (code "43") (name "/OUT_R") (class "Default")
      (node (ref "P5") (pin "1") (pinfunction "1_1") (pintype "passive"))
      (node (ref "R2") (pin "2") (pinfunction "2_2") (pintype "passive"))
      (node (ref "R4") (pin "1") (pinfunction "1_1") (pintype "passive"))
    )
    (net (code "44") (name "/PA0") (class "Default")
      (node (ref "R117") (pin "1") (pinfunction "1_1") (pintype "passive"))
      (node (ref "R22") (pin "2") (pinfunction "2_2") (pintype "passive"))
      (node (ref "U3") (pin "10") (pinfunction "PA0-WKUP_10") (pintype "bidirectional"))
    )
    (net (code "45") (name "/PA1") (class "Default")
      (node (ref "R24") (pin "1") (pinfunction "1_1") (pintype "passive"))
      (node (ref "U3") (pin "11") (pinfunction "PA1_11") (pintype "bidirectional"))
    )
    (net (code "46") (name "/PA2") (class "Default")
      (node (ref "R26") (pin "1") (pinfunction "1_1") (pintype "passive"))
      (node (ref "U3") (pin "12") (pinfunction "PA2_12") (pintype "bidirectional"))
    )
    (net (code "47") (name "/PA3") (class "Default")
      (node (ref "U3") (pin "13") (pinfunction "PA3_13") (pintype "bidirectional"))
    )
    (net (code "48") (name "/PA4") (class "Default")
      (node (ref "U3") (pin "14") (pinfunction "PA4_14") (pintype "bidirectional"))
    )
    (net (code "49") (name "/PA5") (class "Default")
      (node (ref "U3") (pin "15") (pinfunction "PA5_15") (pintype "bidirectional"))
    )
    (net (code "50") (name "/PA6") (class "Default")
      (node (ref "U3") (pin "16") (pinfunction "PA6_16") (pintype "bidirectional"))
    )
    (net (code "51") (name "/PA7") (class "Default")
      (node (ref "R133") (pin "1") (pinfunction "1_1") (pintype "passive"))
      (node (ref "U3") (pin "17") (pinfunction "PA7_17") (pintype "bidirectional"))
    )
    (net (code "52") (name "/PA8") (class "Default")
      (node (ref "R38") (pin "1") (pinfunction "1_1") (pintype "passive"))
      (node (ref "U3") (pin "29") (pinfunction "PA8_29") (pintype "bidirectional"))
    )
    (net (code "53") (name "/PA9") (class "Default")
      (node (ref "R40") (pin "1") (pinfunction "1_1") (pintype "passive"))
      (node (ref "U3") (pin "30") (pinfunction "PA9_30") (pintype "bidirectional"))
    )
    (net (code "54") (name "/PA10") (class "Default")
      (node (ref "R43") (pin "1") (pinfunction "1_1") (pintype "passive"))
      (node (ref "U3") (pin "31") (pinfunction "PA10_31") (pintype "bidirectional"))
    )
    (net (code "55") (name "/PA15") (class "Default")
      (node (ref "R34") (pin "1") (pinfunction "1_1") (pintype "passive"))
      (node (ref "U3") (pin "38") (pinfunction "PA15/JTDI_38") (pintype "bidirectional"))
    )
    (net (code "56") (name "/PB0") (class "Default")
      (node (ref "R100") (pin "1") (pinfunction "1_1") (pintype "passive"))
      (node (ref "R23") (pin "2") (pinfunction "2_2") (pintype "passive"))
      (node (ref "U3") (pin "18") (pinfunction "PB0_18") (pintype "bidirectional"))
    )
    (net (code "57") (name "/PB1") (class "Default")
      (node (ref "U3") (pin "19") (pinfunction "PB1_19") (pintype "bidirectional"))
    )
    (net (code "58") (name "/PB2") (class "Default")
      (node (ref "U3") (pin "20") (pinfunction "PB2/BOOT1_20") (pintype "bidirectional"))
    )
    (net (code "59") (name "/PB3") (class "Default")
      (node (ref "R36") (pin "1") (pinfunction "1_1") (pintype "passive"))
      (node (ref "U3") (pin "39") (pinfunction "PB3/JTDO_39") (pintype "bidirectional"))
    )
    (net (code "60") (name "/PB8") (class "Default")
      (node (ref "R39") (pin "2") (pinfunction "2_2") (pintype "passive"))
      (node (ref "U3") (pin "45") (pinfunction "PB8_45") (pintype "bidirectional"))
    )
    (net (code "61") (name "/PB9") (class "Default")
      (node (ref "R41") (pin "2") (pinfunction "2_2") (pintype "passive"))
      (node (ref "U3") (pin "46") (pinfunction "PB9_46") (pintype "bidirectional"))
    )
    (net (code "62") (name "/PB10") (class "Default")
      (node (ref "R44") (pin "2") (pinfunction "2_2") (pintype "passive"))
      (node (ref "U3") (pin "21") (pinfunction "PB10_21") (pintype "bidirectional"))
    )
    (net (code "63") (name "/PB11") (class "Default")
      (node (ref "D2") (pin "1") (pinfunction "1_1") (pintype "passive"))
      (node (ref "U3") (pin "22") (pinfunction "PB11_22") (pintype "bidirectional"))
    )
    (net (code "64") (name "/PB12") (class "Default")
      (node (ref "R49") (pin "2") (pinfunction "2_2") (pintype "passive"))
      (node (ref "U3") (pin "25") (pinfunction "PB12_25") (pintype "bidirectional"))
    )
    (net (code "65") (name "/PB13") (class "Default")
      (node (ref "R56") (pin "2") (pinfunction "2_2") (pintype "passive"))
      (node (ref "U3") (pin "26") (pinfunction "PB13_26") (pintype "bidirectional"))
    )
    (net (code "66") (name "/PB14") (class "Default")
      (node (ref "R57") (pin "2") (pinfunction "2_2") (pintype "passive"))
      (node (ref "U3") (pin "27") (pinfunction "PB14_27") (pintype "bidirectional"))
    )
    (net (code "67") (name "/PB15") (class "Default")
      (node (ref "R58") (pin "2") (pinfunction "2_2") (pintype "passive"))
      (node (ref "U3") (pin "28") (pinfunction "PB15_28") (pintype "bidirectional"))
    )
    (net (code "68") (name "/PC13") (class "Default")
      (node (ref "R50") (pin "2") (pinfunction "2_2") (pintype "passive"))
      (node (ref "U3") (pin "2") (pinfunction "PC13-TAMPER-RTC_2") (pintype "bidirectional"))
    )
    (net (code "69") (name "/PC14") (class "Default")
      (node (ref "R52") (pin "2") (pinfunction "2_2") (pintype "passive"))
      (node (ref "U3") (pin "3") (pinfunction "PC14-OSC32_IN_3") (pintype "bidirectional"))
    )
    (net (code "70") (name "/PC15") (class "Default")
      (node (ref "R55") (pin "2") (pinfunction "2_2") (pintype "passive"))
      (node (ref "U3") (pin "4") (pinfunction "PC15-OSC32_OUT_4") (pintype "bidirectional"))
    )
    (net (code "71") (name "/PCM_BT") (class "Default")
      (node (ref "IC1") (pin "9") (pinfunction "PCM_9") (pintype "passive"))
      (node (ref "R82") (pin "1") (pinfunction "1_1") (pintype "passive"))
    )
    (net (code "72") (name "/POWER_EN_BT") (class "Default")
      (node (ref "IC1") (pin "15") (pinfunction "POWER_EN_15") (pintype "passive"))
      (node (ref "R101") (pin "1") (pinfunction "1_1") (pintype "passive"))
      (node (ref "R96") (pin "2") (pinfunction "2_2") (pintype "passive"))
    )
    (net (code "73") (name "/POWER_EN_STM") (class "Default")
      (node (ref "R101") (pin "2") (pinfunction "2_2") (pintype "passive"))
      (node (ref "R49") (pin "1") (pinfunction "1_1") (pintype "passive"))
    )
    (net (code "74") (name "/PWR_onOFF") (class "Default")
      (node (ref "P3") (pin "2") (pinfunction "2_2") (pintype "passive"))
      (node (ref "R120") (pin "2") (pinfunction "2_2") (pintype "passive"))
    )
    (net (code "75") (name "/RX_BLUE") (class "Default")
      (node (ref "R40") (pin "2") (pinfunction "2_2") (pintype "passive"))
      (node (ref "R85") (pin "2") (pinfunction "2_2") (pintype "passive"))
    )
    (net (code "76") (name "/SPK_LN1") (class "Default")
      (node (ref "C2") (pin "2") (pinfunction "2_2") (pintype "passive"))
      (node (ref "IC1") (pin "41") (pinfunction "SPK_LN1_41") (pintype "passive"))
    )
    (net (code "77") (name "/SPK_LP1") (class "Default")
      (node (ref "C4") (pin "2") (pinfunction "2_2") (pintype "passive"))
      (node (ref "IC1") (pin "42") (pinfunction "SPK_LP1_42") (pintype "passive"))
    )
    (net (code "78") (name "/SPK_RN1") (class "Default")
      (node (ref "C9") (pin "2") (pinfunction "2_2") (pintype "passive"))
      (node (ref "IC1") (pin "39") (pinfunction "SPK_RN1_39") (pintype "passive"))
    )
    (net (code "79") (name "/SPK_RP1") (class "Default")
      (node (ref "C11") (pin "2") (pinfunction "2_2") (pintype "passive"))
      (node (ref "IC1") (pin "40") (pinfunction "SPK_RP1_40") (pintype "passive"))
    )
    (net (code "80") (name "/STM_NRST") (class "Default")
      (node (ref "C1") (pin "2") (pinfunction "2_2") (pintype "passive"))
      (node (ref "R14") (pin "1") (pinfunction "1_1") (pintype "passive"))
      (node (ref "R31") (pin "1") (pinfunction "1_1") (pintype "passive"))
      (node (ref "R32") (pin "2") (pinfunction "2_2") (pintype "passive"))
      (node (ref "U3") (pin "7") (pinfunction "NRST_7") (pintype "bidirectional"))
    )
    (net (code "81") (name "/STM_SWCLK") (class "Default")
      (node (ref "R9") (pin "1") (pinfunction "1_1") (pintype "passive"))
      (node (ref "U3") (pin "37") (pinfunction "PA14/JTCK/SWCLK_37") (pintype "bidirectional"))
    )
    (net (code "82") (name "/STM_SWDIO") (class "Default")
      (node (ref "R25") (pin "1") (pinfunction "1_1") (pintype "passive"))
      (node (ref "U3") (pin "34") (pinfunction "PA13/JTMS/SWDIO_34") (pintype "bidirectional"))
    )
    (net (code "83") (name "/SWCLK") (class "Default")
      (node (ref "P2") (pin "4") (pinfunction "4_4") (pintype "passive"))
      (node (ref "R9") (pin "2") (pinfunction "2_2") (pintype "passive"))
    )
    (net (code "84") (name "/SWDIO") (class "Default")
      (node (ref "P2") (pin "2") (pinfunction "2_2") (pintype "passive"))
      (node (ref "R25") (pin "2") (pinfunction "2_2") (pintype "passive"))
    )
    (net (code "85") (name "/SW_A") (class "Default")
      (node (ref "R17") (pin "2") (pinfunction "2_2") (pintype "passive"))
      (node (ref "U3") (pin "40") (pinfunction "PB4/JNTRST_40") (pintype "bidirectional"))
    )
    (net (code "86") (name "/SW_B") (class "Default")
      (node (ref "R19") (pin "2") (pinfunction "2_2") (pintype "passive"))
      (node (ref "U3") (pin "41") (pinfunction "PB5_41") (pintype "bidirectional"))
    )
    (net (code "88") (name "/TX_BLUE") (class "Default")
      (node (ref "R43") (pin "2") (pinfunction "2_2") (pintype "passive"))
      (node (ref "R83") (pin "2") (pinfunction "2_2") (pintype "passive"))
    )
    (net (code "89") (name "/VBUS") (class "Default")
      (node (ref "IC1") (pin "12") (pinfunction "VBUS_12") (pintype "passive"))
      (node (ref "R93") (pin "1") (pinfunction "1_1") (pintype "passive"))
    )
    (net (code "90") (name "/VREF_A") (class "Default")
      (node (ref "C12") (pin "1") (pinfunction "1_1") (pintype "passive"))
      (node (ref "C13") (pin "1") (pinfunction "1_1") (pintype "passive"))
      (node (ref "C5") (pin "1") (pinfunction "1_1") (pintype "passive"))
      (node (ref "C6") (pin "1") (pinfunction "1_1") (pintype "passive"))
      (node (ref "R42") (pin "2") (pinfunction "2_2") (pintype "passive"))
      (node (ref "R47") (pin "2") (pinfunction "2_2") (pintype "passive"))
      (node (ref "R51") (pin "2") (pinfunction "2_2") (pintype "passive"))
      (node (ref "R62") (pin "2") (pinfunction "2_2") (pintype "passive"))
    )
    (net (code "91") (name "3.3V") (class "Default")
      (node (ref "C21") (pin "2") (pinfunction "2_2") (pintype "passive"))
      (node (ref "C22") (pin "2") (pinfunction "2_2") (pintype "passive"))
      (node (ref "C23") (pin "2") (pinfunction "2_2") (pintype "passive"))
      (node (ref "C24") (pin "2") (pinfunction "2_2") (pintype "passive"))
      (node (ref "C32") (pin "1") (pinfunction "1_1") (pintype "passive"))
      (node (ref "R29") (pin "2") (pinfunction "2_2") (pintype "passive"))
      (node (ref "R31") (pin "2") (pinfunction "2_2") (pintype "passive"))
      (node (ref "R63") (pin "2") (pinfunction "2_2") (pintype "passive"))
      (node (ref "R64") (pin "2") (pinfunction "2_2") (pintype "passive"))
      (node (ref "R7") (pin "1") (pinfunction "1_1") (pintype "passive"))
      (node (ref "U3") (pin "24") (pinfunction "VDD_1_24") (pintype "power_in"))
      (node (ref "U3") (pin "36") (pinfunction "VDD_2_36") (pintype "power_in"))
      (node (ref "U3") (pin "48") (pinfunction "VDD_3_48") (pintype "power_in"))
      (node (ref "U6") (pin "2") (pinfunction "VOUT_2") (pintype "passive"))
      (node (ref "U6") (pin "4") (pinfunction "VOUT_4") (pintype "passive"))
    )
    (net (code "92") (name "4.2V") (class "Default")
      (node (ref "C36") (pin "1") (pinfunction "1_1") (pintype "passive"))
      (node (ref "C37") (pin "2") (pinfunction "2_2") (pintype "passive"))
      (node (ref "R123") (pin "2") (pinfunction "2_2") (pintype "passive"))
      (node (ref "R124") (pin "2") (pinfunction "2_2") (pintype "passive"))
      (node (ref "R65") (pin "2") (pinfunction "2_2") (pintype "passive"))
      (node (ref "R68") (pin "2") (pinfunction "2_2") (pintype "passive"))
      (node (ref "R90") (pin "2") (pinfunction "2_2") (pintype "passive"))
      (node (ref "R93") (pin "2") (pinfunction "2_2") (pintype "passive"))
      (node (ref "R96") (pin "1") (pinfunction "1_1") (pintype "passive"))
    )
    (net (code "93") (name "5V") (class "Default")
      (node (ref "C29") (pin "1") (pinfunction "1_1") (pintype "passive"))
      (node (ref "C30") (pin "2") (pinfunction "2_2") (pintype "passive"))
      (node (ref "C31") (pin "2") (pinfunction "2_2") (pintype "passive"))
      (node (ref "L2") (pin "1") (pinfunction "1_1") (pintype "passive"))
      (node (ref "R116") (pin "2") (pinfunction "2_2") (pintype "passive"))
      (node (ref "R121") (pin "1") (pinfunction "1_1") (pintype "passive"))
      (node (ref "R98") (pin "1") (pinfunction "1_1") (pintype "passive"))
      (node (ref "U2") (pin "3") (pinfunction "VDD_3") (pintype "power_in"))
      (node (ref "U5") (pin "3") (pinfunction "OUT_3") (pintype "power_in"))
      (node (ref "U6") (pin "3") (pinfunction "VIN_3") (pintype "passive"))
    )
    (net (code "94") (name "5V_AMP") (class "Default")
      (node (ref "C14") (pin "1") (pinfunction "1_1") (pintype "passive"))
      (node (ref "C15") (pin "2") (pinfunction "2_2") (pintype "passive"))
      (node (ref "C16") (pin "2") (pinfunction "2_2") (pintype "passive"))
      (node (ref "L2") (pin "2") (pinfunction "2_2") (pintype "passive"))
      (node (ref "R47") (pin "1") (pinfunction "1_1") (pintype "passive"))
      (node (ref "U1") (pin "16") (pinfunction "VDD_16") (pintype "power_in"))
      (node (ref "U4") (pin "8") (pinfunction "V+_8") (pintype "power_in"))
    )
    (net (code "95") (name "AGND1") (class "Default")
      (node (ref "C27") (pin "1") (pinfunction "1_1") (pintype "passive"))
      (node (ref "C35") (pin "1") (pinfunction "1_1") (pintype "passive"))
      (node (ref "P7") (pin "2") (pinfunction "2_2") (pintype "passive"))
      (node (ref "R27") (pin "2") (pinfunction "2_2") (pintype "passive"))
    )
    (net (code "96") (name "GND") (class "Default")
      (node (ref "C1") (pin "1") (pinfunction "1_1") (pintype "passive"))
      (node (ref "C17") (pin "1") (pinfunction "1_1") (pintype "passive"))
      (node (ref "C21") (pin "1") (pinfunction "1_1") (pintype "passive"))
      (node (ref "C22") (pin "1") (pinfunction "1_1") (pintype "passive"))
      (node (ref "C23") (pin "1") (pinfunction "1_1") (pintype "passive"))
      (node (ref "C24") (pin "1") (pinfunction "1_1") (pintype "passive"))
      (node (ref "C28") (pin "2") (pinfunction "2_2") (pintype "passive"))
      (node (ref "C29") (pin "2") (pinfunction "2_2") (pintype "passive"))
      (node (ref "C30") (pin "1") (pinfunction "1_1") (pintype "passive"))
      (node (ref "C31") (pin "1") (pinfunction "1_1") (pintype "passive"))
      (node (ref "C32") (pin "2") (pinfunction "2_2") (pintype "passive"))
      (node (ref "C36") (pin "2") (pinfunction "2_2") (pintype "passive"))
      (node (ref "C37") (pin "1") (pinfunction "1_1") (pintype "passive"))
      (node (ref "D4") (pin "2") (pinfunction "2_2") (pintype "passive"))
      (node (ref "IC1") (pin "17") (pinfunction "GND_17") (pintype "passive"))
      (node (ref "L4") (pin "1") (pinfunction "1_1") (pintype "passive"))
      (node (ref "P2") (pin "3") (pinfunction "3_3") (pintype "passive"))
      (node (ref "P8") (pin "1") (pinfunction "1_1") (pintype "passive"))
      (node (ref "Q2") (pin "2") (pinfunction "S_2") (pintype "passive"))
      (node (ref "R10") (pin "2") (pinfunction "2_2") (pintype "passive"))
      (node (ref "R100") (pin "2") (pinfunction "2_2") (pintype "passive"))
      (node (ref "R105") (pin "2") (pinfunction "2_2") (pintype "passive"))
      (node (ref "R115") (pin "2") (pinfunction "2_2") (pintype "passive"))
      (node (ref "R117") (pin "2") (pinfunction "2_2") (pintype "passive"))
      (node (ref "R27") (pin "1") (pinfunction "1_1") (pintype "passive"))
      (node (ref "R28") (pin "1") (pinfunction "1_1") (pintype "passive"))
      (node (ref "R32") (pin "1") (pinfunction "1_1") (pintype "passive"))
      (node (ref "R46") (pin "1") (pinfunction "1_1") (pintype "passive"))
      (node (ref "R60") (pin "2") (pinfunction "2_2") (pintype "passive"))
      (node (ref "R98") (pin "2") (pinfunction "2_2") (pintype "passive"))
      (node (ref "U2") (pin "2") (pinfunction "VSS_2") (pintype "power_in"))
      (node (ref "U3") (pin "23") (pinfunction "VSS_1_23") (pintype "power_in"))
      (node (ref "U3") (pin "35") (pinfunction "VSS_2_35") (pintype "power_in"))
      (node (ref "U3") (pin "47") (pinfunction "VSS_3_47") (pintype "power_in"))
      (node (ref "U3") (pin "8") (pinfunction "VSSA_8") (pintype "power_in"))
      (node (ref "U5") (pin "4") (pinfunction "GND_4") (pintype "power_in"))
      (node (ref "U6") (pin "1") (pinfunction "GND_1") (pintype "passive"))
    )
    (net (code "97") (name "GND_A") (class "Default")
      (node (ref "C12") (pin "2") (pinfunction "2_2") (pintype "passive"))
      (node (ref "C13") (pin "2") (pinfunction "2_2") (pintype "passive"))
      (node (ref "C14") (pin "2") (pinfunction "2_2") (pintype "passive"))
      (node (ref "C15") (pin "1") (pinfunction "1_1") (pintype "passive"))
      (node (ref "C16") (pin "1") (pinfunction "1_1") (pintype "passive"))
      (node (ref "C5") (pin "2") (pinfunction "2_2") (pintype "passive"))
      (node (ref "C6") (pin "2") (pinfunction "2_2") (pintype "passive"))
      (node (ref "L1") (pin "1") (pinfunction "1_1") (pintype "passive"))
      (node (ref "L4") (pin "2") (pinfunction "2_2") (pintype "passive"))
      (node (ref "R131") (pin "2") (pinfunction "2_2") (pintype "passive"))
      (node (ref "R132") (pin "2") (pinfunction "2_2") (pintype "passive"))
      (node (ref "R20") (pin "2") (pinfunction "2_2") (pintype "passive"))
      (node (ref "R51") (pin "1") (pinfunction "1_1") (pintype "passive"))
      (node (ref "U1") (pin "7") (pinfunction "VEE_7") (pintype "power_in"))
      (node (ref "U1") (pin "8") (pinfunction "VSS_8") (pintype "power_in"))
      (node (ref "U4") (pin "4") (pinfunction "V-_4") (pintype "power_in"))
    )
    (net (code "98") (name "GND_OUT") (class "Default")
      (node (ref "L1") (pin "2") (pinfunction "2_2") (pintype "passive"))
      (node (ref "P1") (pin "1") (pinfunction "1_1") (pintype "passive"))
      (node (ref "P1") (pin "2") (pinfunction "2_2") (pintype "passive"))
      (node (ref "R33") (pin "1") (pinfunction "1_1") (pintype "passive"))
      (node (ref "R4") (pin "2") (pinfunction "2_2") (pintype "passive"))
    )
    (net (code "99") (name "Net-(C2-Pad1)") (class "Default")
      (node (ref "C2") (pin "1") (pinfunction "1_1") (pintype "passive"))
      (node (ref "R35") (pin "2") (pinfunction "2_2") (pintype "passive"))
    )
    (net (code "100") (name "Net-(C4-Pad1)") (class "Default")
      (node (ref "C4") (pin "1") (pinfunction "1_1") (pintype "passive"))
      (node (ref "R37") (pin "2") (pinfunction "2_2") (pintype "passive"))
    )
    (net (code "101") (name "Net-(C9-Pad1)") (class "Default")
      (node (ref "C9") (pin "1") (pinfunction "1_1") (pintype "passive"))
      (node (ref "R59") (pin "2") (pinfunction "2_2") (pintype "passive"))
    )
    (net (code "102") (name "Net-(C11-Pad1)") (class "Default")
      (node (ref "C11") (pin "1") (pinfunction "1_1") (pintype "passive"))
      (node (ref "R61") (pin "2") (pinfunction "2_2") (pintype "passive"))
    )
    (net (code "103") (name "Net-(C27-Pad2)") (class "Default")
      (node (ref "C27") (pin "2") (pinfunction "2_2") (pintype "passive"))
      (node (ref "C40") (pin "1") (pinfunction "1_1") (pintype "passive"))
      (node (ref "L5") (pin "1") (pinfunction "1_1") (pintype "passive"))
      (node (ref "R78") (pin "2") (pinfunction "2_2") (pintype "passive"))
    )
    (net (code "104") (name "Net-(C34-Pad1)") (class "Default")
      (node (ref "C34") (pin "1") (pinfunction "1_1") (pintype "passive"))
      (node (ref "C35") (pin "2") (pinfunction "2_2") (pintype "passive"))
      (node (ref "L6") (pin "1") (pinfunction "1_1") (pintype "passive"))
      (node (ref "R119") (pin "2") (pinfunction "2_2") (pintype "passive"))
    )
    (net (code "105") (name "Net-(D1-Pad1)") (class "Default")
      (node (ref "D1") (pin "1") (pinfunction "1_1") (pintype "passive"))
      (node (ref "R124") (pin "1") (pinfunction "1_1") (pintype "passive"))
    )
    (net (code "106") (name "Net-(D2-Pad2)") (class "Default")
      (node (ref "D2") (pin "2") (pinfunction "2_2") (pintype "passive"))
      (node (ref "R46") (pin "2") (pinfunction "2_2") (pintype "passive"))
    )
    (net (code "107") (name "Net-(D3-Pad1)") (class "Default")
      (node (ref "D3") (pin "1") (pinfunction "1_1") (pintype "passive"))
      (node (ref "R68") (pin "1") (pinfunction "1_1") (pintype "passive"))
    )
    (net (code "108") (name "Net-(D4-Pad1)") (class "Default")
      (node (ref "D4") (pin "1") (pinfunction "1_1") (pintype "passive"))
      (node (ref "R116") (pin "1") (pinfunction "1_1") (pintype "passive"))
    )
    (net (code "109") (name "Net-(D5-A)") (class "Default")
      (node (ref "D5") (pin "1") (pinfunction "A_1") (pintype "passive"))
      (node (ref "P3") (pin "3") (pinfunction "3_3") (pintype "passive"))
    )
    (net (code "110") (name "Net-(D5-K)") (class "Default")
      (node (ref "D5") (pin "2") (pinfunction "K_2") (pintype "passive"))
      (node (ref "R99") (pin "1") (pinfunction "1_1") (pintype "passive"))
    )
    (net (code "111") (name "Net-(D6-Pad1)") (class "Default")
      (node (ref "D6") (pin "1") (pinfunction "1_1") (pintype "passive"))
      (node (ref "R65") (pin "1") (pinfunction "1_1") (pintype "passive"))
    )
    (net (code "112") (name "Net-(IC1-BAT)") (class "Default")
      (node (ref "IC1") (pin "14") (pinfunction "BAT_14") (pintype "passive"))
      (node (ref "R90") (pin "1") (pinfunction "1_1") (pintype "passive"))
    )
    (net (code "113") (name "Net-(IC1-RX)") (class "Default")
      (node (ref "IC1") (pin "11") (pinfunction "RX_11") (pintype "passive"))
      (node (ref "R85") (pin "1") (pinfunction "1_1") (pintype "passive"))
    )
    (net (code "114") (name "Net-(IC1-TX)") (class "Default")
      (node (ref "IC1") (pin "10") (pinfunction "TX_10") (pintype "passive"))
      (node (ref "R83") (pin "1") (pinfunction "1_1") (pintype "passive"))
    )
    (net (code "115") (name "Net-(L10-Pad1)") (class "Default")
      (node (ref "L10") (pin "1") (pinfunction "1_1") (pintype "passive"))
      (node (ref "R99") (pin "2") (pinfunction "2_2") (pintype "passive"))
    )
    (net (code "116") (name "Net-(P2-Pad5)") (class "Default")
      (node (ref "P2") (pin "5") (pinfunction "5_5") (pintype "passive"))
      (node (ref "R7") (pin "2") (pinfunction "2_2") (pintype "passive"))
    )
    (net (code "117") (name "Net-(P2-Pad6)") (class "Default")
      (node (ref "P2") (pin "6") (pinfunction "6_6") (pintype "passive"))
      (node (ref "R5") (pin "2") (pinfunction "2_2") (pintype "passive"))
    )
    (net (code "118") (name "Net-(P2-Pad7)") (class "Default")
      (node (ref "P2") (pin "7") (pinfunction "7_7") (pintype "passive"))
      (node (ref "R1") (pin "2") (pinfunction "2_2") (pintype "passive"))
    )
    (net (code "119") (name "Net-(P3-Pad1)") (class "Default")
      (node (ref "P3") (pin "1") (pinfunction "1_1") (pintype "passive"))
      (node (ref "R105") (pin "1") (pinfunction "1_1") (pintype "passive"))
    )
    (net (code "120") (name "Net-(P8-Pad2)") (class "Default")
      (node (ref "P8") (pin "2") (pinfunction "2_2") (pintype "passive"))
      (node (ref "R82") (pin "2") (pinfunction "2_2") (pintype "passive"))
    )
    (net (code "121") (name "Net-(P8-Pad3)") (class "Default")
      (node (ref "P8") (pin "3") (pinfunction "3_3") (pintype "passive"))
      (node (ref "R80") (pin "2") (pinfunction "2_2") (pintype "passive"))
    )
    (net (code "122") (name "Net-(P8-Pad4)") (class "Default")
      (node (ref "P8") (pin "4") (pinfunction "4_4") (pintype "passive"))
      (node (ref "R77") (pin "2") (pinfunction "2_2") (pintype "passive"))
    )
    (net (code "123") (name "Net-(P8-Pad5)") (class "Default")
      (node (ref "P8") (pin "5") (pinfunction "5_5") (pintype "passive"))
      (node (ref "R75") (pin "2") (pinfunction "2_2") (pintype "passive"))
    )
    (net (code "124") (name "Net-(P8-Pad6)") (class "Default")
      (node (ref "P8") (pin "6") (pinfunction "6_6") (pintype "passive"))
      (node (ref "R73") (pin "2") (pinfunction "2_2") (pintype "passive"))
    )
    (net (code "125") (name "Net-(Q1-G)") (class "Default")
      (node (ref "Q1") (pin "1") (pinfunction "G_1") (pintype "passive"))
      (node (ref "Q2") (pin "3") (pinfunction "D_3") (pintype "passive"))
      (node (ref "R118") (pin "1") (pinfunction "1_1") (pintype "passive"))
    )
    (net (code "126") (name "Net-(Q2-G)") (class "Default")
      (node (ref "Q2") (pin "1") (pinfunction "G_1") (pintype "passive"))
      (node (ref "R120") (pin "1") (pinfunction "1_1") (pintype "passive"))
      (node (ref "R28") (pin "2") (pinfunction "2_2") (pintype "passive"))
    )
    (net (code "127") (name "Net-(R115-Pad1)") (class "Default")
      (node (ref "R115") (pin "1") (pinfunction "1_1") (pintype "passive"))
      (node (ref "R56") (pin "1") (pinfunction "1_1") (pintype "passive"))
      (node (ref "R57") (pin "1") (pinfunction "1_1") (pintype "passive"))
      (node (ref "R58") (pin "1") (pinfunction "1_1") (pintype "passive"))
    )
    (net (code "128") (name "Net-(R121-Pad2)") (class "Default")
      (node (ref "R121") (pin "2") (pinfunction "2_2") (pintype "passive"))
      (node (ref "R122") (pin "1") (pinfunction "1_1") (pintype "passive"))
      (node (ref "R29") (pin "1") (pinfunction "1_1") (pintype "passive"))
    )
    (net (code "129") (name "Net-(R122-Pad2)") (class "Default")
      (node (ref "R122") (pin "2") (pinfunction "2_2") (pintype "passive"))
      (node (ref "R123") (pin "1") (pinfunction "1_1") (pintype "passive"))
    )
    (net (code "130") (name "Net-(U1-COM_X_O{slash}I)") (class "Default")
      (node (ref "R2") (pin "1") (pinfunction "1_1") (pintype "passive"))
      (node (ref "U1") (pin "13") (pinfunction "COM_X_O/I_13") (pintype "passive"))
    )
    (net (code "131") (name "Net-(U1-COM_Y_O{slash}I)") (class "Default")
      (node (ref "R12") (pin "1") (pinfunction "1_1") (pintype "passive"))
      (node (ref "U1") (pin "3") (pinfunction "COM_Y_O/I_3") (pintype "passive"))
    )
    (net (code "132") (name "Net-(U1-INH)") (class "Default")
      (node (ref "R20") (pin "1") (pinfunction "1_1") (pintype "passive"))
      (node (ref "U1") (pin "6") (pinfunction "INH_6") (pintype "input"))
    )
    (net (code "133") (name "Net-(U1-X_CHAN_I{slash}O_0)") (class "Default")
      (node (ref "R3") (pin "2") (pinfunction "2_2") (pintype "passive"))
      (node (ref "U1") (pin "12") (pinfunction "X_CHAN_I/O_0_12") (pintype "passive"))
    )
    (net (code "134") (name "Net-(U1-X_CHAN_I{slash}O_2)") (class "Default")
      (node (ref "R18") (pin "2") (pinfunction "2_2") (pintype "passive"))
      (node (ref "U1") (pin "15") (pinfunction "X_CHAN_I/O_2_15") (pintype "passive"))
    )
    (net (code "135") (name "Net-(U1-X_CHAN_I{slash}O_3)") (class "Default")
      (node (ref "R6") (pin "2") (pinfunction "2_2") (pintype "passive"))
      (node (ref "U1") (pin "11") (pinfunction "X_CHAN_I/O_3_11") (pintype "passive"))
    )
    (net (code "136") (name "Net-(U1-Y_CHAN_I{slash}O_0)") (class "Default")
      (node (ref "R13") (pin "2") (pinfunction "2_2") (pintype "passive"))
      (node (ref "U1") (pin "1") (pinfunction "Y_CHAN_I/O_0_1") (pintype "passive"))
    )
    (net (code "137") (name "Net-(U1-Y_CHAN_I{slash}O_2)") (class "Default")
      (node (ref "R128") (pin "2") (pinfunction "2_2") (pintype "passive"))
      (node (ref "U1") (pin "2") (pinfunction "Y_CHAN_I/O_2_2") (pintype "passive"))
    )
    (net (code "138") (name "Net-(U1-Y_CHAN_I{slash}O_3)") (class "Default")
      (node (ref "R16") (pin "2") (pinfunction "2_2") (pintype "passive"))
      (node (ref "U1") (pin "4") (pinfunction "Y_CHAN_I/O_3_4") (pintype "passive"))
    )
    (net (code "139") (name "Net-(U2-CANH)") (class "Default")
      (node (ref "P4") (pin "1") (pinfunction "1_1") (pintype "passive"))
      (node (ref "R11") (pin "1") (pinfunction "1_1") (pintype "passive"))
      (node (ref "U2") (pin "7") (pinfunction "CANH_7") (pintype "bidirectional"))
    )
    (net (code "140") (name "Net-(U2-CANL)") (class "Default")
      (node (ref "P4") (pin "2") (pinfunction "2_2") (pintype "passive"))
      (node (ref "R11") (pin "2") (pinfunction "2_2") (pintype "passive"))
      (node (ref "U2") (pin "6") (pinfunction "CANL_6") (pintype "bidirectional"))
    )
    (net (code "141") (name "Net-(U2-RS)") (class "Default")
      (node (ref "R10") (pin "1") (pinfunction "1_1") (pintype "passive"))
      (node (ref "U2") (pin "8") (pinfunction "RS_8") (pintype "input"))
    )
    (net (code "142") (name "Net-(U2-RXD)") (class "Default")
      (node (ref "R15") (pin "1") (pinfunction "1_1") (pintype "passive"))
      (node (ref "U2") (pin "4") (pinfunction "RXD_4") (pintype "output"))
    )
    (net (code "143") (name "Net-(U2-TXD)") (class "Default")
      (node (ref "R8") (pin "1") (pinfunction "1_1") (pintype "passive"))
      (node (ref "U2") (pin "1") (pinfunction "TXD_1") (pintype "input"))
    )
    (net (code "144") (name "Net-(U3-BOOT0)") (class "Default")
      (node (ref "R60") (pin "1") (pinfunction "1_1") (pintype "passive"))
      (node (ref "U3") (pin "44") (pinfunction "BOOT0_44") (pintype "input"))
    )
    (net (code "145") (name "Net-(U3-PA11)") (class "Default")
      (node (ref "R45") (pin "1") (pinfunction "1_1") (pintype "passive"))
      (node (ref "U3") (pin "32") (pinfunction "PA11_32") (pintype "bidirectional"))
    )
    (net (code "146") (name "Net-(U3-PA12)") (class "Default")
      (node (ref "R48") (pin "1") (pinfunction "1_1") (pintype "passive"))
      (node (ref "U3") (pin "33") (pinfunction "PA12_33") (pintype "bidirectional"))
    )
    (net (code "147") (name "Net-(U3-VBAT)") (class "Default")
      (node (ref "R63") (pin "1") (pinfunction "1_1") (pintype "passive"))
      (node (ref "U3") (pin "1") (pinfunction "VBAT_1") (pintype "power_in"))
    )
    (net (code "148") (name "Net-(U3-VDDA)") (class "Default")
      (node (ref "C17") (pin "2") (pinfunction "2_2") (pintype "passive"))
      (node (ref "R64") (pin "1") (pinfunction "1_1") (pintype "passive"))
      (node (ref "U3") (pin "9") (pinfunction "VDDA_9") (pintype "power_in"))
    )
    (net (code "149") (name "Net-(U4A-IN+)") (class "Default")
      (node (ref "R37") (pin "1") (pinfunction "1_1") (pintype "passive"))
      (node (ref "R42") (pin "1") (pinfunction "1_1") (pintype "passive"))
      (node (ref "U4") (pin "3") (pinfunction "IN+_3") (pintype "input"))
    )
    (net (code "150") (name "Net-(U4A-IN-)") (class "Default")
      (node (ref "C25") (pin "2") (pinfunction "2_2") (pintype "passive"))
      (node (ref "R21") (pin "2") (pinfunction "2_2") (pintype "passive"))
      (node (ref "R35") (pin "1") (pinfunction "1_1") (pintype "passive"))
      (node (ref "U4") (pin "2") (pinfunction "IN-_2") (pintype "input"))
    )
    (net (code "151") (name "Net-(U4A-OUT)") (class "Default")
      (node (ref "C25") (pin "1") (pinfunction "1_1") (pintype "passive"))
      (node (ref "C3") (pin "1") (pinfunction "1_1") (pintype "passive"))
      (node (ref "R21") (pin "1") (pinfunction "1_1") (pintype "passive"))
      (node (ref "U4") (pin "1") (pinfunction "OUT_1") (pintype "output"))
    )
    (net (code "152") (name "Net-(U4B-IN+)") (class "Default")
      (node (ref "R61") (pin "1") (pinfunction "1_1") (pintype "passive"))
      (node (ref "R62") (pin "1") (pinfunction "1_1") (pintype "passive"))
      (node (ref "U4") (pin "5") (pinfunction "IN+_5") (pintype "input"))
    )
    (net (code "153") (name "Net-(U4B-IN-)") (class "Default")
      (node (ref "C26") (pin "2") (pinfunction "2_2") (pintype "passive"))
      (node (ref "R53") (pin "2") (pinfunction "2_2") (pintype "passive"))
      (node (ref "R59") (pin "1") (pinfunction "1_1") (pintype "passive"))
      (node (ref "U4") (pin "6") (pinfunction "IN-_6") (pintype "input"))
    )
    (net (code "154") (name "Net-(U4B-OUT)") (class "Default")
      (node (ref "C10") (pin "1") (pinfunction "1_1") (pintype "passive"))
      (node (ref "C26") (pin "1") (pinfunction "1_1") (pintype "passive"))
      (node (ref "R53") (pin "1") (pinfunction "1_1") (pintype "passive"))
      (node (ref "U4") (pin "7") (pinfunction "OUT_7") (pintype "output"))
    )
    (net (code "155") (name "unconnected-(IC1-1V8-Pad16)") (class "Default")
      (node (ref "IC1") (pin "16") (pinfunction "1V8_16") (pintype "passive"))
    )
    (net (code "156") (name "unconnected-(IC1-AIO0-Pad4)") (class "Default")
      (node (ref "IC1") (pin "4") (pinfunction "AIO0_4") (pintype "passive"))
    )
    (net (code "157") (name "unconnected-(IC1-ANT-Pad43)") (class "Default")
      (node (ref "IC1") (pin "43") (pinfunction "ANT_43") (pintype "passive"))
    )
    (net (code "158") (name "unconnected-(IC1-BAT_SENSE-Pad19)") (class "Default")
      (node (ref "IC1") (pin "19") (pinfunction "BAT_SENSE_19") (pintype "passive"))
    )
    (net (code "159") (name "unconnected-(IC1-CHG_EXT-Pad18)") (class "Default")
      (node (ref "IC1") (pin "18") (pinfunction "CHG_EXT_18") (pintype "passive"))
    )
    (net (code "160") (name "unconnected-(IC1-PIO16-Pad20)") (class "Default")
      (node (ref "IC1") (pin "20") (pinfunction "PIO16_20") (pintype "passive"))
    )
    (net (code "161") (name "unconnected-(IC1-PIO17-Pad21)") (class "Default")
      (node (ref "IC1") (pin "21") (pinfunction "PIO17_21") (pintype "passive"))
    )
    (net (code "162") (name "unconnected-(IC1-PIO_2-Pad22)") (class "Default")
      (node (ref "IC1") (pin "22") (pinfunction "PIO_2_22") (pintype "passive"))
    )
    (net (code "163") (name "unconnected-(IC1-PIO_3-Pad23)") (class "Default")
      (node (ref "IC1") (pin "23") (pinfunction "PIO_3_23") (pintype "passive"))
    )
    (net (code "164") (name "unconnected-(IC1-RST#-Pad13)") (class "Default")
      (node (ref "IC1") (pin "13") (pinfunction "RST#_13") (pintype "passive"))
    )
    (net (code "165") (name "unconnected-(IC1-USB_N-Pad24)") (class "Default")
      (node (ref "IC1") (pin "24") (pinfunction "USB_N_24") (pintype "passive"))
    )
    (net (code "166") (name "unconnected-(IC1-USB_P-Pad25)") (class "Default")
      (node (ref "IC1") (pin "25") (pinfunction "USB_P_25") (pintype "passive"))
    )
    (net (code "167") (name "unconnected-(R38-Pad2)") (class "Default")
      (node (ref "R38") (pin "2") (pinfunction "2_2") (pintype "passive"))
    )
    (net (code "168") (name "unconnected-(U1-X_CHAN_I{slash}O_1-Pad14)") (class "Default")
      (node (ref "U1") (pin "14") (pinfunction "X_CHAN_I/O_1_14") (pintype "passive"))
    )
    (net (code "169") (name "unconnected-(U1-Y_CHAN_I{slash}O_1-Pad5)") (class "Default")
      (node (ref "U1") (pin "5") (pinfunction "Y_CHAN_I/O_1_5") (pintype "passive"))
    )
    (net (code "170") (name "unconnected-(U2-VREF-Pad5)") (class "Default")
      (node (ref "U2") (pin "5") (pinfunction "VREF_5") (pintype "output"))
    )
    (net (code "171") (name "unconnected-(U3-OSC_IN{slash}PD0-Pad5)") (class "Default")
      (node (ref "U3") (pin "5") (pinfunction "OSC_IN/PD0_5") (pintype "input"))
    )
    (net (code "172") (name "unconnected-(U3-OSC_OUT{slash}PD1-Pad6)") (class "Default")
      (node (ref "U3") (pin "6") (pinfunction "OSC_OUT/PD1_6") (pintype "output"))
    )
  )
)
